# bricotester.net
KiCad netlist of a schematic drawn in EAGLE
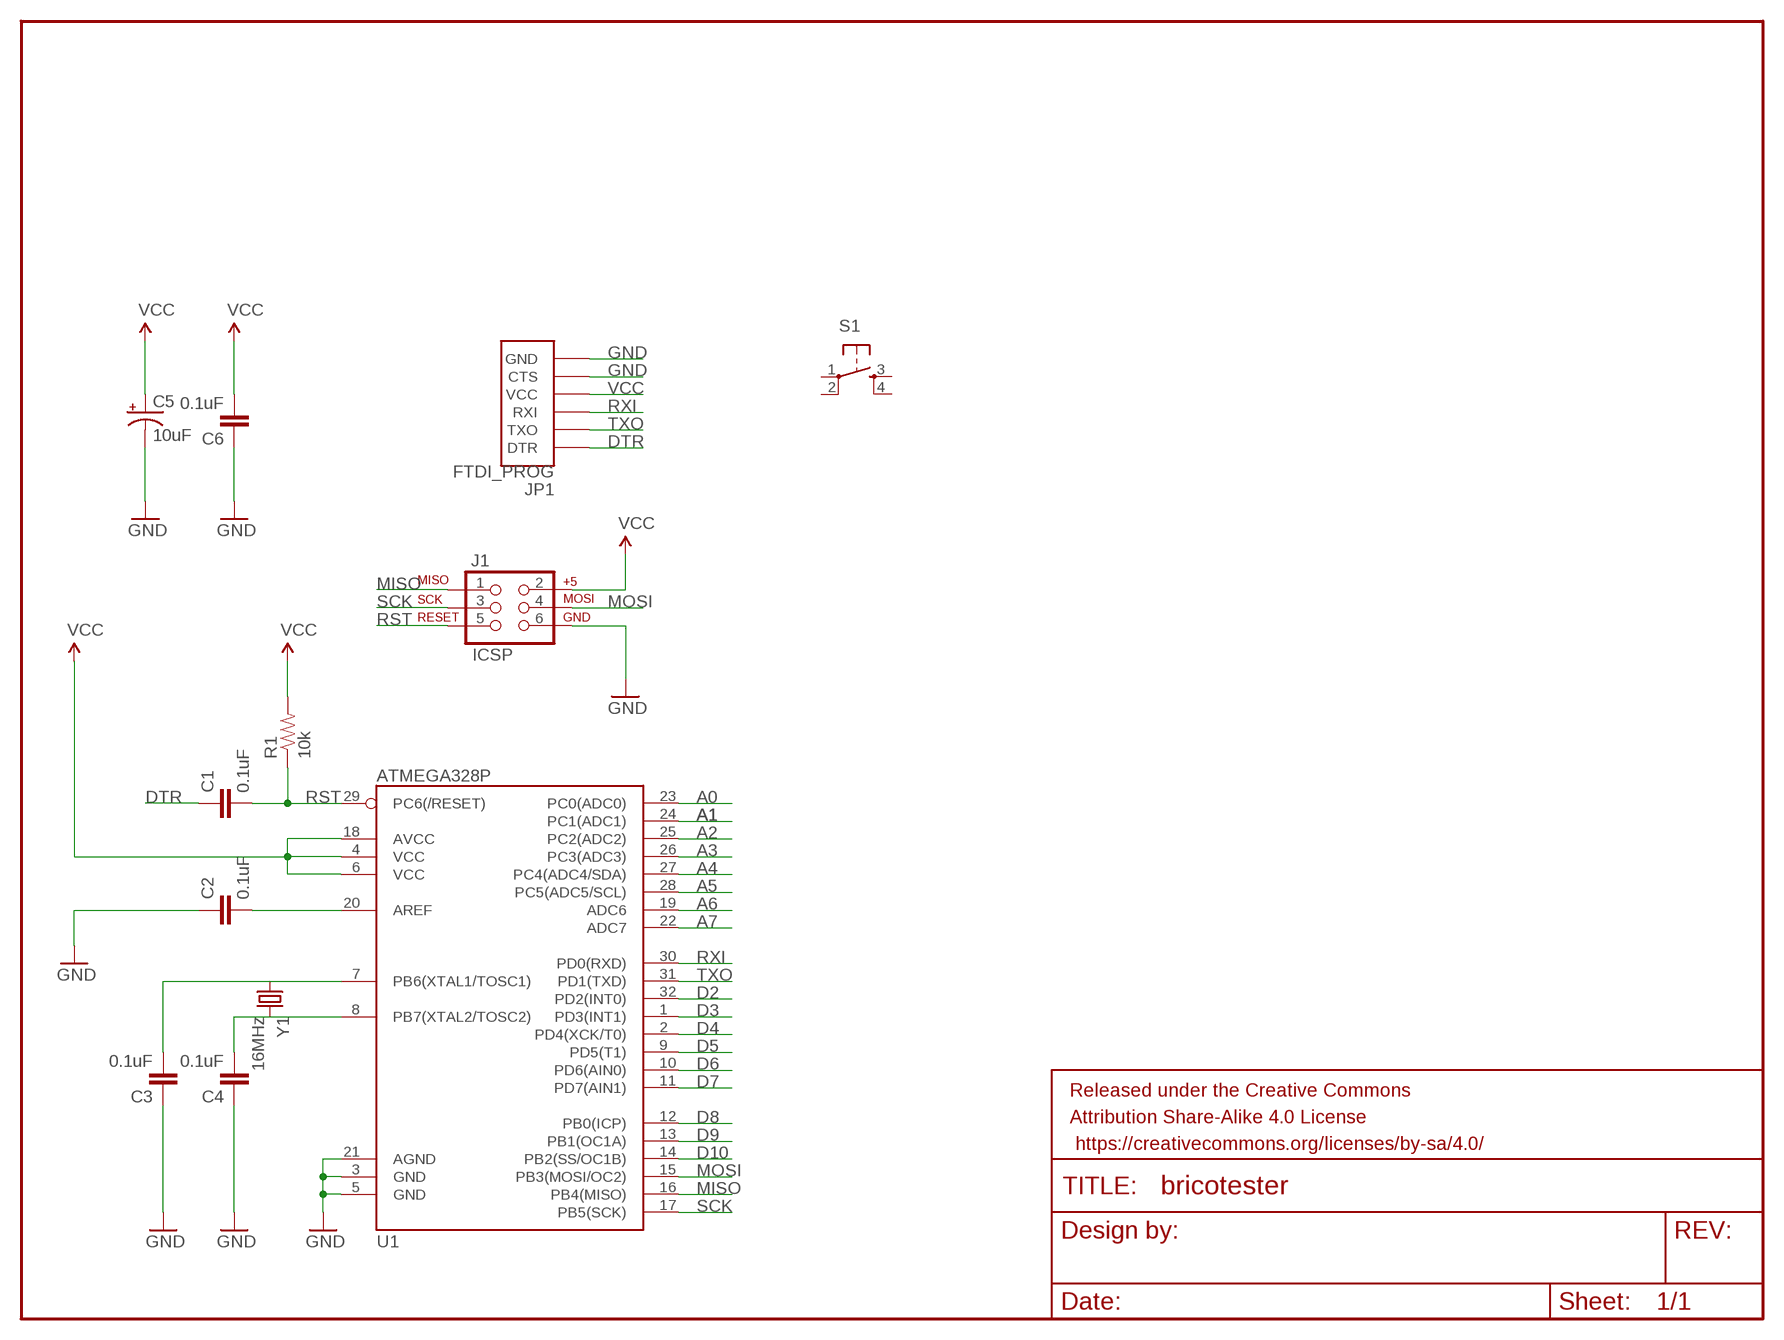
[diagram p0: schematic, sheet 1]

(export (version "E")
  (design (tool "Eeschema 10.0.6"))
  (components
    (comp (ref "C1")
      (value "0.1uF")
      (footprint "eagle-import:1206")
      (libsource (lib "eagle-import") (part "CAP1206"))
    )
    (comp (ref "C2")
      (value "0.1uF")
      (footprint "eagle-import:1206")
      (libsource (lib "eagle-import") (part "CAP1206"))
    )
    (comp (ref "C3")
      (value "0.1uF")
      (footprint "eagle-import:1206")
      (libsource (lib "eagle-import") (part "CAP1206"))
    )
    (comp (ref "C4")
      (value "0.1uF")
      (footprint "eagle-import:1206")
      (libsource (lib "eagle-import") (part "CAP1206"))
    )
    (comp (ref "C5")
      (value "10uF")
      (footprint "eagle-import:PANASONIC_D")
      (libsource (lib "eagle-import") (part "CAP_POLD"))
    )
    (comp (ref "C6")
      (value "0.1uF")
      (footprint "eagle-import:1206")
      (libsource (lib "eagle-import") (part "CAP1206"))
    )
    (comp (ref "FRAME1")
      (value "FRAME-LETTER")
      (footprint "eagle-import:CREATIVE_COMMONS")
      (libsource (lib "eagle-import") (part "FRAME-LETTER"))
    )
    (comp (ref "J1")
      (value "ICSP")
      (footprint "eagle-import:2X3")
      (libsource (lib "eagle-import") (part "AVR_SPI_PRG_6PTH"))
    )
    (comp (ref "JP1")
      (value "FTDI_PROG")
      (footprint "eagle-import:FTDI_DEVICE_SIDE")
      (libsource (lib "eagle-import") (part "FTDI_DEVICE"))
    )
    (comp (ref "R1")
      (value "10k")
      (footprint "eagle-import:0805")
      (libsource (lib "eagle-import") (part "RESISTOR0805-RES"))
    )
    (comp (ref "S1")
      (value "TAC_SWITCHSMD")
      (footprint "eagle-import:TACTILE_SWITCH_SMD")
      (libsource (lib "eagle-import") (part "TAC_SWITCHSMD"))
    )
    (comp (ref "U1")
      (value "ATMEGA328P")
      (footprint "eagle-import:TQFP32-08")
      (libsource (lib "eagle-import") (part "ATMEGA328_SMT"))
    )
    (comp (ref "Y1")
      (value "16MHz")
      (footprint "eagle-import:HC49UP")
      (libsource (lib "eagle-import") (part "CRYSTALSMD"))
    )
  )
  (nets
    (net (code "1") (name "/A0") (class "Default")
      (node (ref "U1") (pin "23") (pinfunction "PC0(ADC0)_23") (pintype "bidirectional"))
    )
    (net (code "2") (name "/A1") (class "Default")
      (node (ref "U1") (pin "24") (pinfunction "PC1(ADC1)_24") (pintype "bidirectional"))
    )
    (net (code "3") (name "/A2") (class "Default")
      (node (ref "U1") (pin "25") (pinfunction "PC2(ADC2)_25") (pintype "bidirectional"))
    )
    (net (code "4") (name "/A3") (class "Default")
      (node (ref "U1") (pin "26") (pinfunction "PC3(ADC3)_26") (pintype "bidirectional"))
    )
    (net (code "5") (name "/A4") (class "Default")
      (node (ref "U1") (pin "27") (pinfunction "PC4(ADC4/SDA)_27") (pintype "bidirectional"))
    )
    (net (code "6") (name "/A5") (class "Default")
      (node (ref "U1") (pin "28") (pinfunction "PC5(ADC5/SCL)_28") (pintype "bidirectional"))
    )
    (net (code "7") (name "/A6") (class "Default")
      (node (ref "U1") (pin "19") (pinfunction "ADC6_19") (pintype "bidirectional"))
    )
    (net (code "8") (name "/A7") (class "Default")
      (node (ref "U1") (pin "22") (pinfunction "ADC7_22") (pintype "bidirectional"))
    )
    (net (code "9") (name "/D2") (class "Default")
      (node (ref "U1") (pin "32") (pinfunction "PD2(INT0)_32") (pintype "bidirectional"))
    )
    (net (code "10") (name "/D3") (class "Default")
      (node (ref "U1") (pin "1") (pinfunction "PD3(INT1)_1") (pintype "bidirectional"))
    )
    (net (code "11") (name "/D4") (class "Default")
      (node (ref "U1") (pin "2") (pinfunction "PD4(XCK/T0)_2") (pintype "bidirectional"))
    )
    (net (code "12") (name "/D5") (class "Default")
      (node (ref "U1") (pin "9") (pinfunction "PD5(T1)_9") (pintype "bidirectional"))
    )
    (net (code "13") (name "/D6") (class "Default")
      (node (ref "U1") (pin "10") (pinfunction "PD6(AIN0)_10") (pintype "bidirectional"))
    )
    (net (code "14") (name "/D7") (class "Default")
      (node (ref "U1") (pin "11") (pinfunction "PD7(AIN1)_11") (pintype "bidirectional"))
    )
    (net (code "15") (name "/D8") (class "Default")
      (node (ref "U1") (pin "12") (pinfunction "PB0(ICP)_12") (pintype "bidirectional"))
    )
    (net (code "16") (name "/D9") (class "Default")
      (node (ref "U1") (pin "13") (pinfunction "PB1(OC1A)_13") (pintype "bidirectional"))
    )
    (net (code "17") (name "/D10") (class "Default")
      (node (ref "U1") (pin "14") (pinfunction "PB2(SS/OC1B)_14") (pintype "bidirectional"))
    )
    (net (code "18") (name "/DTR") (class "Default")
      (node (ref "C1") (pin "1") (pinfunction "1_1") (pintype "passive"))
      (node (ref "JP1") (pin "P$1") (pinfunction "DTR_P$1") (pintype "bidirectional"))
    )
    (net (code "19") (name "/MISO") (class "Default")
      (node (ref "J1") (pin "1") (pinfunction "1_1") (pintype "passive"))
      (node (ref "U1") (pin "16") (pinfunction "PB4(MISO)_16") (pintype "bidirectional"))
    )
    (net (code "20") (name "/MOSI") (class "Default")
      (node (ref "J1") (pin "4") (pinfunction "4_4") (pintype "passive"))
      (node (ref "U1") (pin "15") (pinfunction "PB3(MOSI/OC2)_15") (pintype "bidirectional"))
    )
    (net (code "21") (name "/RST") (class "Default")
      (node (ref "C1") (pin "2") (pinfunction "2_2") (pintype "passive"))
      (node (ref "J1") (pin "5") (pinfunction "5_5") (pintype "passive"))
      (node (ref "R1") (pin "1") (pinfunction "1_1") (pintype "passive"))
      (node (ref "U1") (pin "29") (pinfunction "PC6(/RESET)_29") (pintype "bidirectional"))
    )
    (net (code "22") (name "/RXI") (class "Default")
      (node (ref "JP1") (pin "P$3") (pinfunction "RXI_P$3") (pintype "bidirectional"))
      (node (ref "U1") (pin "30") (pinfunction "PD0(RXD)_30") (pintype "bidirectional"))
    )
    (net (code "23") (name "/SCK") (class "Default")
      (node (ref "J1") (pin "3") (pinfunction "3_3") (pintype "passive"))
      (node (ref "U1") (pin "17") (pinfunction "PB5(SCK)_17") (pintype "bidirectional"))
    )
    (net (code "24") (name "/TXO") (class "Default")
      (node (ref "JP1") (pin "P$2") (pinfunction "TXO_P$2") (pintype "bidirectional"))
      (node (ref "U1") (pin "31") (pinfunction "PD1(TXD)_31") (pintype "bidirectional"))
    )
    (net (code "25") (name "GND") (class "Default")
      (node (ref "C2") (pin "1") (pinfunction "1_1") (pintype "passive"))
      (node (ref "C3") (pin "1") (pinfunction "1_1") (pintype "passive"))
      (node (ref "C4") (pin "1") (pinfunction "1_1") (pintype "passive"))
      (node (ref "C5") (pin "-") (pinfunction "-_-") (pintype "passive"))
      (node (ref "C6") (pin "1") (pinfunction "1_1") (pintype "passive"))
      (node (ref "J1") (pin "6") (pinfunction "6_6") (pintype "passive"))
      (node (ref "JP1") (pin "P$5") (pinfunction "CTS_P$5") (pintype "bidirectional"))
      (node (ref "JP1") (pin "P$6") (pinfunction "GND_P$6") (pintype "bidirectional"))
      (node (ref "U1") (pin "21") (pinfunction "AGND_21") (pintype "bidirectional"))
      (node (ref "U1") (pin "3") (pinfunction "GND_3") (pintype "bidirectional"))
      (node (ref "U1") (pin "5") (pinfunction "GND_5") (pintype "bidirectional"))
    )
    (net (code "26") (name "Net-(U1-AREF)") (class "Default")
      (node (ref "C2") (pin "2") (pinfunction "2_2") (pintype "passive"))
      (node (ref "U1") (pin "20") (pinfunction "AREF_20") (pintype "bidirectional"))
    )
    (net (code "27") (name "Net-(U1-PB6(XTAL1{slash}TOSC1))") (class "Default")
      (node (ref "C3") (pin "2") (pinfunction "2_2") (pintype "passive"))
      (node (ref "U1") (pin "7") (pinfunction "PB6(XTAL1/TOSC1)_7") (pintype "bidirectional"))
      (node (ref "Y1") (pin "1") (pinfunction "1_1") (pintype "passive"))
    )
    (net (code "28") (name "Net-(U1-PB7(XTAL2{slash}TOSC2))") (class "Default")
      (node (ref "C4") (pin "2") (pinfunction "2_2") (pintype "passive"))
      (node (ref "U1") (pin "8") (pinfunction "PB7(XTAL2/TOSC2)_8") (pintype "bidirectional"))
      (node (ref "Y1") (pin "2") (pinfunction "2_2") (pintype "passive"))
    )
    (net (code "29") (name "VCC") (class "Default")
      (node (ref "C5") (pin "+") (pinfunction "+_+") (pintype "passive"))
      (node (ref "C6") (pin "2") (pinfunction "2_2") (pintype "passive"))
      (node (ref "J1") (pin "2") (pinfunction "2_2") (pintype "passive"))
      (node (ref "JP1") (pin "P$4") (pinfunction "VCC_P$4") (pintype "bidirectional"))
      (node (ref "R1") (pin "2") (pinfunction "2_2") (pintype "passive"))
      (node (ref "U1") (pin "18") (pinfunction "AVCC_18") (pintype "bidirectional"))
      (node (ref "U1") (pin "4") (pinfunction "VCC_4") (pintype "bidirectional"))
      (node (ref "U1") (pin "6") (pinfunction "VCC_6") (pintype "bidirectional"))
    )
    (net (code "30") (name "unconnected-(S1-Pad1)") (class "Default")
      (node (ref "S1") (pin "1") (pinfunction "1_1") (pintype "passive"))
    )
    (net (code "31") (name "unconnected-(S1-Pad2)") (class "Default")
      (node (ref "S1") (pin "2") (pinfunction "2_2") (pintype "passive"))
    )
    (net (code "32") (name "unconnected-(S1-Pad3)") (class "Default")
      (node (ref "S1") (pin "3") (pinfunction "3_3") (pintype "passive"))
    )
    (net (code "33") (name "unconnected-(S1-Pad4)") (class "Default")
      (node (ref "S1") (pin "4") (pinfunction "4_4") (pintype "passive"))
    )
  )
)
